# Power_Charge_USB.net
KiCad netlist of a schematic drawn in Altium Designer
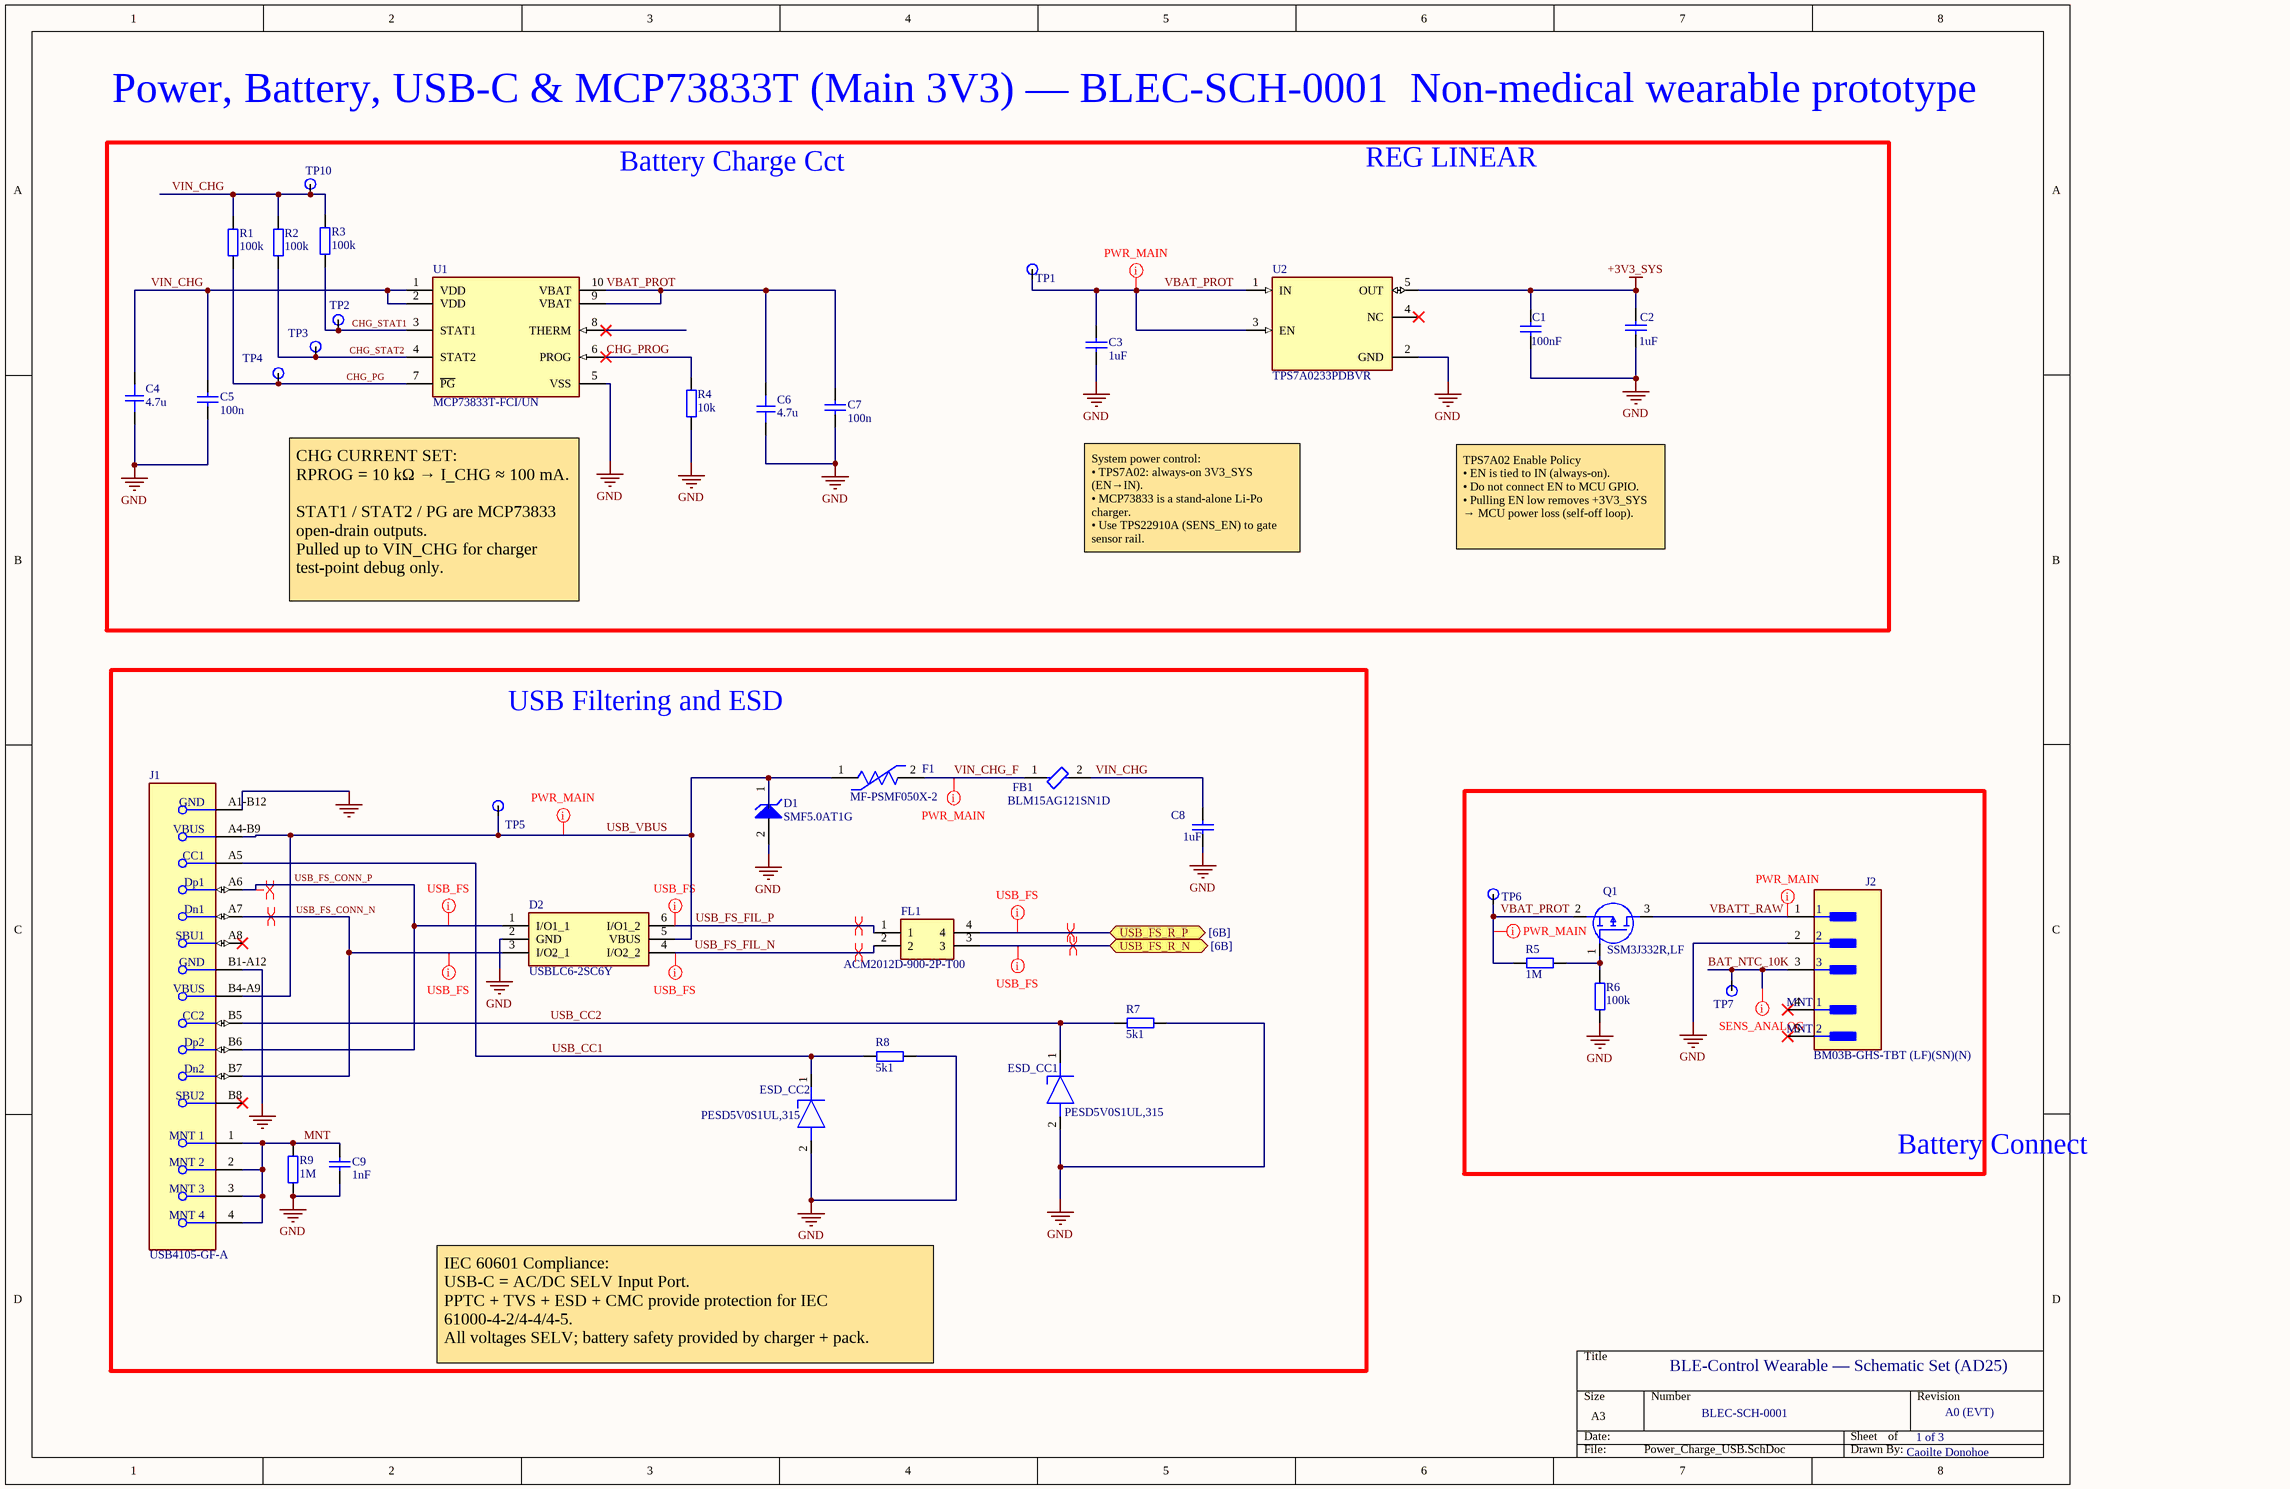
[diagram p0: Power_Charge_USB.SchDoc]

(export (version "E")
  (design (tool "Eeschema 10.0.6"))
  (components
    (comp (ref "C1")
      (value "100nF")
      (footprint "CAP_0402")
      (description "Ceramic Chip Capacitor 0402")
      (fields (field (name "VOLTAGE") "10V") (field (name "TOLERANCE") "10%"))
      (libsource (lib "BLE-Control") (part "C_0402"))
    )
    (comp (ref "C2")
      (value "1uF")
      (footprint "CAP_0402")
      (description "Ceramic Chip Capacitor 0402")
      (fields (field (name "VOLTAGE") "10V") (field (name "TOLERANCE") "10%"))
      (libsource (lib "BLE-Control") (part "C_0402"))
    )
    (comp (ref "C3")
      (value "1uF")
      (footprint "CAP_0402")
      (description "Ceramic Chip Capacitor 0402")
      (fields (field (name "VOLTAGE") "10V") (field (name "TOLERANCE") "10%"))
      (libsource (lib "BLE-Control") (part "C_0402"))
    )
    (comp (ref "C4")
      (value "4.7u")
      (footprint "CAP_0603")
      (description "Capacitor SMD 0603")
      (libsource (lib "BLE-Control") (part "CAP_0603"))
    )
    (comp (ref "C5")
      (value "100n")
      (footprint "CAP_0402")
      (description "Ceramic Chip Capacitor 0402")
      (fields (field (name "VOLTAGE") "10V") (field (name "TOLERANCE") "10%"))
      (libsource (lib "BLE-Control") (part "C_0402"))
    )
    (comp (ref "C6")
      (value "4.7u")
      (footprint "CAP_0603")
      (description "Capacitor SMD 0603")
      (libsource (lib "BLE-Control") (part "CAP_0603"))
    )
    (comp (ref "C7")
      (value "100n")
      (footprint "CAP_0402")
      (description "Ceramic Chip Capacitor 0402")
      (fields (field (name "VOLTAGE") "10V") (field (name "TOLERANCE") "10%"))
      (libsource (lib "BLE-Control") (part "C_0402"))
    )
    (comp (ref "C8")
      (value "1uF")
      (footprint "CAP_0402")
      (description "Ceramic Chip Capacitor 0402")
      (fields (field (name "VOLTAGE") "10V") (field (name "TOLERANCE") "10%"))
      (libsource (lib "BLE-Control") (part "C_0402"))
    )
    (comp (ref "C9")
      (value "1nF")
      (footprint "CAP_0402")
      (description "Ceramic Chip Capacitor 0402")
      (fields (field (name "VOLTAGE") "10V") (field (name "TOLERANCE") "10%"))
      (libsource (lib "BLE-Control") (part "C_0402"))
    )
    (comp (ref "D1")
      (value "SMF5.0AT1G")
      (footprint "ONSC-SOD-123FL-2-498_V")
      (description "200 W Transient Voltage Suppressor, 2-Pin SOD-123FL, Pb-Free, Tape and Reel")
      (fields (field (name "MANUFACTURER") "On Semiconductor"))
      (libsource (lib "BLE-Control") (part "CMP-1061-00612-1"))
    )
    (comp (ref "D2")
      (value "USBLC6-2SC6Y")
      (footprint "SamacSys:SOT95P280X145-6N")
      (description "Diode")
      (fields (field (name "MOUSER PART NUMBER") "511-USBLC6-2SC6Y"))
      (libsource (lib "*") (part "USBLC6-2SC6Y"))
    )
    (comp (ref "ESD_CC1")
      (value "PESD5V0S1UL,315")
      (footprint "PESD5V0S1BL315")
      (description "Diode ESD (Uni-directional)")
      (fields (field (name "MOUSER PART NUMBER") "771-PESD5V0S1UL315"))
      (libsource (lib "*") (part "PESD5V0S1UL,315"))
    )
    (comp (ref "ESD_CC2")
      (value "PESD5V0S1UL,315")
      (footprint "PESD5V0S1BL315")
      (description "Diode ESD (Uni-directional)")
      (fields (field (name "MOUSER PART NUMBER") "771-PESD5V0S1UL315"))
      (libsource (lib "*") (part "PESD5V0S1UL,315"))
    )
    (comp (ref "F1")
      (value "MF-PSMF050X-2")
      (footprint "FP-MF-PSMF-MFG")
      (description "PTC RESET FUSE 6V 500MA 0805")
      (fields
        (field (name "MANUFACTURER") "Bourns Inc.")
        (field (name "OCTOPART") "https://octopart.com/mf-psmf050x-2-bourns-7483438")
      )
      (libsource (lib "BLE-Control") (part "CMP-07400-000013-1"))
    )
    (comp (ref "FB1")
      (value "BLM15AG121SN1D")
      (footprint "FP-BLM15-0_05-IPC_A")
      (description "Chip Ferrite Bead, 0402, 120Ω @ 100MHz, 0.19Ω, 25%, 550mA")
      (fields (field (name "TOLERANCE") "25%"))
      (libsource (lib "BLE-Control") (part "CMP-0686-00170-4"))
    )
    (comp (ref "FL1")
      (value "ACM2012D-900-2P-T00")
      (footprint "SamacSys:ACM2012D9002PT00")
      (description "Filter")
      (fields (field (name "MOUSER PART NUMBER") "810-ACM2012D9002PT00"))
      (libsource (lib "BLE-Control") (part "ACM2012D-900-2P-T00"))
    )
    (comp (ref "J1")
      (value "USB4105-GF-A")
      (footprint "BLE-Control:FP-USB4105-GF-A-MFG")
      (description "CONN RCPT USB2.0 TYPEC 5A")
      (fields
        (field (name "MANUFACTURER") "GCT")
        (field (name "OCTOPART") "https://octopart.com/usb4105-gf-a-gct-106627878")
      )
      (libsource (lib "BLE-Control") (part "CMP-245163-000001-1"))
    )
    (comp (ref "J2")
      (value "BM03B-GHS-TBT (LF)(SN)(N)")
      (footprint "FP-BM03B-GHS-TBT_LF_SN-MFG")
      (description "CONN HEADER SMD 3POS 1.25MM")
      (libsource (lib "BLE-Control") (part "CMP-17439-000616-1"))
    )
    (comp (ref "Q1")
      (value "SSM3J332R,LF")
      (footprint "SamacSys:SSM3J332RLFT")
      (description "MOSFET (P-Channel)")
      (fields (field (name "MOUSER PART NUMBER") "757-SSM3J332RLF"))
      (libsource (lib "*") (part "SSM3J332R,LF"))
    )
    (comp (ref "R1")
      (value "100k")
      (footprint "RES_0603")
      (description "Resistor SMD 0603")
      (libsource (lib "BLE-Control") (part "RES_0603"))
    )
    (comp (ref "R2")
      (value "100k")
      (footprint "RES_0603")
      (description "Resistor SMD 0603")
      (libsource (lib "BLE-Control") (part "RES_0603"))
    )
    (comp (ref "R3")
      (value "100k")
      (footprint "RES_0603")
      (description "Resistor SMD 0603")
      (libsource (lib "BLE-Control") (part "RES_0603"))
    )
    (comp (ref "R4")
      (value "10k")
      (footprint "BLE-Control:RES_0402")
      (description "Resistor SMD 0402")
      (libsource (lib "BLE-Control") (part "R_0402"))
    )
    (comp (ref "R5")
      (value "1M")
      (footprint "RES_0402")
      (description "Resistor SMD 0402")
      (libsource (lib "BLE-Control") (part "R_0402"))
    )
    (comp (ref "R6")
      (value "100k")
      (footprint "RES_0402")
      (description "Resistor SMD 0402")
      (libsource (lib "BLE-Control") (part "R_0402"))
    )
    (comp (ref "R7")
      (value "5k1")
      (footprint "BLE-Control:RES_0402")
      (description "Resistor SMD 0402")
      (libsource (lib "BLE-Control") (part "R_0402"))
    )
    (comp (ref "R8")
      (value "5k1")
      (footprint "RES_0402")
      (description "Resistor SMD 0402")
      (libsource (lib "BLE-Control") (part "R_0402"))
    )
    (comp (ref "R9")
      (value "1M")
      (footprint "RES_0402")
      (description "Resistor SMD 0402")
      (libsource (lib "BLE-Control") (part "R_0402"))
    )
    (comp (ref "TP1")
      (value "TestPoint")
      (footprint "PCBComponent_1")
      (libsource (lib "BLE-Control") (part "TestPoint"))
    )
    (comp (ref "TP2")
      (value "USB_VBUS")
      (footprint "PCBComponent_1")
      (libsource (lib "BLE-Control") (part "TestPoint"))
    )
    (comp (ref "TP3")
      (value "USB_VBUS")
      (footprint "PCBComponent_1")
      (libsource (lib "BLE-Control") (part "TestPoint"))
    )
    (comp (ref "TP4")
      (value "USB_VBUS")
      (footprint "PCBComponent_1")
      (libsource (lib "BLE-Control") (part "TestPoint"))
    )
    (comp (ref "TP5")
      (value "USB_VBUS")
      (footprint "PCBComponent_1")
      (libsource (lib "BLE-Control") (part "TestPoint"))
    )
    (comp (ref "TP6")
      (value "VBAT_PROT")
      (footprint "PCBComponent_1")
      (libsource (lib "BLE-Control") (part "TestPoint"))
    )
    (comp (ref "TP7")
      (value "BAT_NTC_10K")
      (footprint "PCBComponent_1")
      (libsource (lib "BLE-Control") (part "TestPoint"))
    )
    (comp (ref "TP10")
      (value "~")
      (footprint "TP_VIA_0p75")
      (libsource (lib "BLE-Control") (part "TestPoint"))
    )
    (comp (ref "U1")
      (value "MCP73833T-FCI/UN")
      (footprint "FP-C04-021-IPC_B")
      (description "IC LI-ION/LI-POLY CTRLR 10MSOP")
      (libsource (lib "BLE-Control") (part "MCP73833T-FCI-UN"))
    )
    (comp (ref "U2")
      (value "TPS7A0233PDBVR")
      (footprint "FP-DBV0005A-IPC_A")
      (description "IC REG LINEAR 3.3V 200MA SOT23-5")
      (libsource (lib "BLE-Control") (part "CMP-04917-000286-1"))
    )
  )
  (nets
    (net (code "1") (name "+3V3_SYS") (class "Default")
      (node (ref "C1") (pin "2") (pinfunction "2_2") (pintype "passive"))
      (node (ref "C2") (pin "2") (pinfunction "2_2") (pintype "passive"))
      (node (ref "U2") (pin "5") (pinfunction "OUT_5") (pintype "bidirectional"))
    )
    (net (code "2") (name "/BAT_NTC_10K") (class "Default")
      (node (ref "J2") (pin "3") (pinfunction "3_3") (pintype "passive"))
      (node (ref "TP7") (pin "1") (pinfunction "0_1") (pintype "passive"))
    )
    (net (code "3") (name "/CHG_PG") (class "Default")
      (node (ref "R1") (pin "1") (pinfunction "1_1") (pintype "passive"))
      (node (ref "TP4") (pin "1") (pinfunction "0_1") (pintype "passive"))
      (node (ref "U1") (pin "7") (pinfunction "~{PG}_7") (pintype "open_collector"))
    )
    (net (code "4") (name "/CHG_PROG") (class "Default")
      (node (ref "R4") (pin "2") (pinfunction "2_2") (pintype "passive"))
      (node (ref "U1") (pin "6") (pinfunction "PROG_6") (pintype "input"))
    )
    (net (code "5") (name "/CHG_STAT1") (class "Default")
      (node (ref "R3") (pin "1") (pinfunction "1_1") (pintype "passive"))
      (node (ref "TP2") (pin "1") (pinfunction "0_1") (pintype "passive"))
      (node (ref "U1") (pin "3") (pinfunction "STAT1_3") (pintype "open_collector"))
    )
    (net (code "6") (name "/CHG_STAT2") (class "Default")
      (node (ref "R2") (pin "1") (pinfunction "1_1") (pintype "passive"))
      (node (ref "TP3") (pin "1") (pinfunction "0_1") (pintype "passive"))
      (node (ref "U1") (pin "4") (pinfunction "STAT2_4") (pintype "open_collector"))
    )
    (net (code "7") (name "/MNT") (class "Default")
      (node (ref "C9") (pin "2") (pinfunction "2_2") (pintype "passive"))
      (node (ref "J1") (pin "1") (pinfunction "MNT_1_1") (pintype "power_in"))
      (node (ref "J1") (pin "2") (pinfunction "MNT_2_2") (pintype "power_in"))
      (node (ref "J1") (pin "3") (pinfunction "MNT_3_3") (pintype "power_in"))
      (node (ref "J1") (pin "4") (pinfunction "MNT_4_4") (pintype "power_in"))
      (node (ref "R9") (pin "2") (pinfunction "2_2") (pintype "passive"))
    )
    (net (code "8") (name "/USB_CC1") (class "Default")
      (node (ref "ESD_CC2") (pin "1") (pinfunction "K_1") (pintype "passive"))
      (node (ref "J1") (pin "A5") (pinfunction "CC1_A5") (pintype "power_in"))
      (node (ref "R8") (pin "1") (pinfunction "1_1") (pintype "passive"))
    )
    (net (code "9") (name "/USB_CC2") (class "Default")
      (node (ref "ESD_CC1") (pin "1") (pinfunction "K_1") (pintype "passive"))
      (node (ref "J1") (pin "B5") (pinfunction "CC2_B5") (pintype "bidirectional"))
      (node (ref "R7") (pin "1") (pinfunction "1_1") (pintype "passive"))
    )
    (net (code "10") (name "/USB_FS_CONN_N") (class "Default")
      (node (ref "D2") (pin "3") (pinfunction "I/O2_1_3") (pintype "passive"))
      (node (ref "J1") (pin "A7") (pinfunction "Dn1_A7") (pintype "bidirectional"))
      (node (ref "J1") (pin "B7") (pinfunction "Dn2_B7") (pintype "bidirectional"))
    )
    (net (code "11") (name "/USB_FS_CONN_P") (class "Default")
      (node (ref "D2") (pin "1") (pinfunction "I/O1_1_1") (pintype "passive"))
      (node (ref "J1") (pin "A6") (pinfunction "Dp1_A6") (pintype "bidirectional"))
      (node (ref "J1") (pin "B6") (pinfunction "Dp2_B6") (pintype "bidirectional"))
    )
    (net (code "12") (name "/USB_FS_FIL_N") (class "Default")
      (node (ref "D2") (pin "4") (pinfunction "I/O2_2_4") (pintype "passive"))
      (node (ref "FL1") (pin "2") (pinfunction "2_2") (pintype "passive"))
    )
    (net (code "13") (name "/USB_FS_FIL_P") (class "Default")
      (node (ref "D2") (pin "6") (pinfunction "I/O1_2_6") (pintype "passive"))
      (node (ref "FL1") (pin "1") (pinfunction "1_1") (pintype "passive"))
    )
    (net (code "14") (name "/USB_FS_R_N") (class "Default")
      (node (ref "FL1") (pin "3") (pinfunction "3_3") (pintype "passive"))
    )
    (net (code "15") (name "/USB_FS_R_P") (class "Default")
      (node (ref "FL1") (pin "4") (pinfunction "4_4") (pintype "passive"))
    )
    (net (code "16") (name "/USB_VBUS") (class "Default")
      (node (ref "D1") (pin "1") (pinfunction "K_1") (pintype "passive"))
      (node (ref "D2") (pin "5") (pinfunction "VBUS_5") (pintype "passive"))
      (node (ref "F1") (pin "1") (pinfunction "1_1") (pintype "passive"))
      (node (ref "J1") (pin "A4-B9") (pinfunction "VBUS_A4-B9") (pintype "power_in"))
      (node (ref "J1") (pin "B4-A9") (pinfunction "VBUS_B4-A9") (pintype "passive"))
      (node (ref "TP5") (pin "1") (pinfunction "0_1") (pintype "passive"))
    )
    (net (code "17") (name "/VBATT_RAW") (class "Default")
      (node (ref "J2") (pin "1") (pinfunction "1_1") (pintype "passive"))
      (node (ref "Q1") (pin "3") (pinfunction "D_3") (pintype "passive"))
    )
    (net (code "18") (name "/VBAT_PROT") (class "Default")
      (node (ref "C3") (pin "2") (pinfunction "2_2") (pintype "passive"))
      (node (ref "C6") (pin "2") (pinfunction "2_2") (pintype "passive"))
      (node (ref "C7") (pin "2") (pinfunction "2_2") (pintype "passive"))
      (node (ref "Q1") (pin "2") (pinfunction "S_2") (pintype "passive"))
      (node (ref "R5") (pin "1") (pinfunction "1_1") (pintype "passive"))
      (node (ref "TP1") (pin "1") (pinfunction "0_1") (pintype "passive"))
      (node (ref "TP6") (pin "1") (pinfunction "0_1") (pintype "passive"))
      (node (ref "U1") (pin "10") (pinfunction "VBAT_10") (pintype "power_in"))
      (node (ref "U1") (pin "9") (pinfunction "VBAT_9") (pintype "power_in"))
      (node (ref "U2") (pin "1") (pinfunction "IN_1") (pintype "input"))
      (node (ref "U2") (pin "3") (pinfunction "EN_3") (pintype "input"))
    )
    (net (code "19") (name "/VIN_CHG") (class "Default")
      (node (ref "C4") (pin "2") (pinfunction "2_2") (pintype "passive"))
      (node (ref "C5") (pin "2") (pinfunction "2_2") (pintype "passive"))
      (node (ref "C8") (pin "2") (pinfunction "2_2") (pintype "passive"))
      (node (ref "FB1") (pin "2") (pinfunction "2_2") (pintype "passive"))
      (node (ref "R1") (pin "2") (pinfunction "2_2") (pintype "passive"))
      (node (ref "R2") (pin "2") (pinfunction "2_2") (pintype "passive"))
      (node (ref "R3") (pin "2") (pinfunction "2_2") (pintype "passive"))
      (node (ref "TP10") (pin "1") (pinfunction "0_1") (pintype "passive"))
      (node (ref "U1") (pin "1") (pinfunction "VDD_1") (pintype "power_in"))
      (node (ref "U1") (pin "2") (pinfunction "VDD_2") (pintype "power_in"))
    )
    (net (code "20") (name "/VIN_CHG_F") (class "Default")
      (node (ref "F1") (pin "2") (pinfunction "2_2") (pintype "passive"))
      (node (ref "FB1") (pin "1") (pinfunction "1_1") (pintype "passive"))
    )
    (net (code "21") (name "GND") (class "Default")
      (node (ref "C1") (pin "1") (pinfunction "1_1") (pintype "passive"))
      (node (ref "C2") (pin "1") (pinfunction "1_1") (pintype "passive"))
      (node (ref "C3") (pin "1") (pinfunction "1_1") (pintype "passive"))
      (node (ref "C4") (pin "1") (pinfunction "1_1") (pintype "passive"))
      (node (ref "C5") (pin "1") (pinfunction "1_1") (pintype "passive"))
      (node (ref "C6") (pin "1") (pinfunction "1_1") (pintype "passive"))
      (node (ref "C7") (pin "1") (pinfunction "1_1") (pintype "passive"))
      (node (ref "C8") (pin "1") (pinfunction "1_1") (pintype "passive"))
      (node (ref "C9") (pin "1") (pinfunction "1_1") (pintype "passive"))
      (node (ref "D1") (pin "2") (pinfunction "A_2") (pintype "passive"))
      (node (ref "D2") (pin "2") (pinfunction "GND_2") (pintype "passive"))
      (node (ref "ESD_CC1") (pin "2") (pinfunction "A_2") (pintype "passive"))
      (node (ref "ESD_CC2") (pin "2") (pinfunction "A_2") (pintype "passive"))
      (node (ref "J1") (pin "A1-B12") (pinfunction "GND_A1-B12") (pintype "passive"))
      (node (ref "J1") (pin "B1-A12") (pinfunction "GND_B1-A12") (pintype "passive"))
      (node (ref "J2") (pin "2") (pinfunction "2_2") (pintype "passive"))
      (node (ref "R4") (pin "1") (pinfunction "1_1") (pintype "passive"))
      (node (ref "R6") (pin "1") (pinfunction "1_1") (pintype "passive"))
      (node (ref "R7") (pin "2") (pinfunction "2_2") (pintype "passive"))
      (node (ref "R8") (pin "2") (pinfunction "2_2") (pintype "passive"))
      (node (ref "R9") (pin "1") (pinfunction "1_1") (pintype "passive"))
      (node (ref "U1") (pin "5") (pinfunction "VSS_5") (pintype "power_in"))
      (node (ref "U2") (pin "2") (pinfunction "GND_2") (pintype "power_in"))
    )
    (net (code "22") (name "Net-(Q1-G)") (class "Default")
      (node (ref "Q1") (pin "1") (pinfunction "G_1") (pintype "passive"))
      (node (ref "R5") (pin "2") (pinfunction "2_2") (pintype "passive"))
      (node (ref "R6") (pin "2") (pinfunction "2_2") (pintype "passive"))
    )
    (net (code "23") (name "unconnected-(J1-SBU1-PadA8)") (class "Default")
      (node (ref "J1") (pin "A8") (pinfunction "SBU1_A8") (pintype "bidirectional+no_connect"))
    )
    (net (code "24") (name "unconnected-(J1-SBU2-PadB8)") (class "Default")
      (node (ref "J1") (pin "B8") (pinfunction "SBU2_B8") (pintype "power_in+no_connect"))
    )
    (net (code "25") (name "unconnected-(J2-MNT_1-Pad4)") (class "Default")
      (node (ref "J2") (pin "4") (pinfunction "MNT_1_4") (pintype "passive+no_connect"))
    )
    (net (code "26") (name "unconnected-(J2-MNT_2-Pad5)") (class "Default")
      (node (ref "J2") (pin "5") (pinfunction "MNT_2_5") (pintype "passive+no_connect"))
    )
    (net (code "27") (name "unconnected-(U1-THERM-Pad8)") (class "Default")
      (node (ref "U1") (pin "8") (pinfunction "THERM_8") (pintype "input+no_connect"))
    )
    (net (code "28") (name "unconnected-(U2-NC-Pad4)") (class "Default")
      (node (ref "U2") (pin "4") (pinfunction "NC_4") (pintype "passive+no_connect"))
    )
  )
)
